# usb.net
KiCad netlist of a schematic drawn in Altium Designer
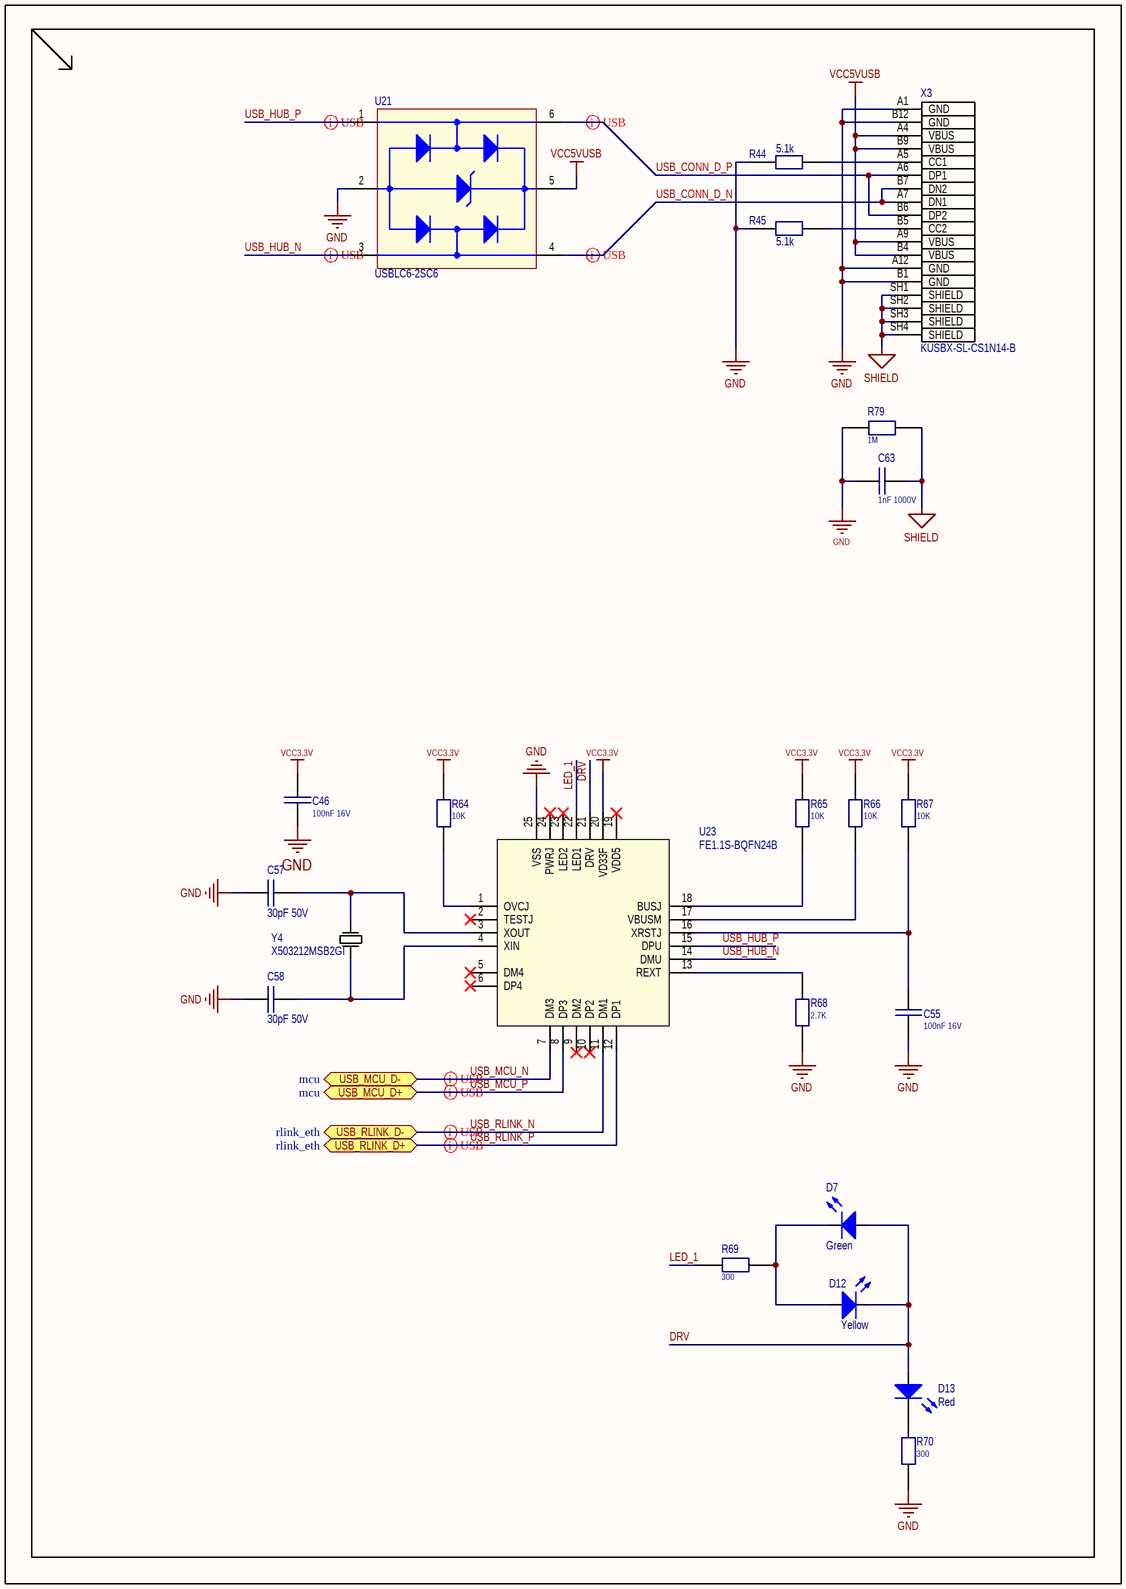
[diagram p0: usb.SchDoc]

(export (version "E")
  (design (tool "Eeschema 10.0.6"))
  (components
    (comp (ref "C46")
      (value "100nF 16V")
      (footprint "C_0402")
      (description "Capacitor")
      (fields (field (name "PART") "CC0402KRX7R7BB104") (field (name "ALTERNATIVE PART") "CC0402KRX5R7BB104"))
      (libsource (lib "capacitors") (part "C0402"))
    )
    (comp (ref "C55")
      (value "100nF 16V")
      (footprint "C_0402")
      (description "Capacitor")
      (fields (field (name "PART") "CC0402KRX7R7BB104") (field (name "ALTERNATIVE PART") "CC0402KRX5R7BB104"))
      (libsource (lib "capacitors") (part "C0402"))
    )
    (comp (ref "C57")
      (value "30pF 50V")
      (footprint "C_0603")
      (description "Capacitor")
      (fields (field (name "PART") "CC0603JRNPO9BN300") (field (name "JLCPCB PART") "C113797"))
      (libsource (lib "capacitors") (part "CAP_SMD"))
    )
    (comp (ref "C58")
      (value "30pF 50V")
      (footprint "C_0603")
      (description "Capacitor")
      (fields (field (name "PART") "CC0603JRNPO9BN300") (field (name "JLCPCB PART") "C113797"))
      (libsource (lib "capacitors") (part "CAP_SMD"))
    )
    (comp (ref "C63")
      (value "1nF 1000V")
      (footprint "C_1206")
      (description "Capacitor")
      (fields (field (name "PART") "CC1206KKX7RCBB102") (field (name "ALTERNATIVE PART") "CL31B102KIFNNNE"))
      (libsource (lib "capacitors") (part "C1206"))
    )
    (comp (ref "D7")
      (value "Green")
      (footprint "LED_0603")
      (description "LED")
      (fields (field (name "PART") "FYLS-0603PGC") (field (name "ALTERNATIVE PART") "KP-1608CGCK"))
      (libsource (lib "led_lcd") (part "LED_SMT_0603"))
    )
    (comp (ref "D12")
      (value "Yellow")
      (footprint "LED_0603")
      (description "LED")
      (fields (field (name "PART") "FYLS-0603PGC") (field (name "ALTERNATIVE PART") "KP-1608CGCK"))
      (libsource (lib "led_lcd") (part "LED_SMT_0603"))
    )
    (comp (ref "D13")
      (value "Red")
      (footprint "LED_0603")
      (description "LED")
      (fields (field (name "PART") "FYLS-0603PGC") (field (name "ALTERNATIVE PART") "KP-1608CGCK"))
      (libsource (lib "led_lcd") (part "LED_SMT_0603"))
    )
    (comp (ref "R44")
      (value "5.1k")
      (footprint "R_0603")
      (description "Resistor")
      (fields (field (name "PART") "RC0603JR-075K1L") (field (name "JLCPCB PART") "C14677"))
      (libsource (lib "resistors") (part "RES_SMD"))
    )
    (comp (ref "R45")
      (value "5.1k")
      (footprint "R_0603")
      (description "Resistor")
      (fields (field (name "PART") "RC0603JR-075K1L") (field (name "JLCPCB PART") "C14677"))
      (libsource (lib "resistors") (part "RES_SMD"))
    )
    (comp (ref "R64")
      (value "10K")
      (footprint "R_0402")
      (description "Resistor")
      (fields (field (name "PART") "RC0402JR-0710KL") (field (name "JLCPCB PART") "C60489"))
      (libsource (lib "resistors") (part "R0402"))
    )
    (comp (ref "R65")
      (value "10K")
      (footprint "R_0402")
      (description "Resistor")
      (fields (field (name "PART") "RC0402JR-0710KL") (field (name "JLCPCB PART") "C60489"))
      (libsource (lib "resistors") (part "R0402"))
    )
    (comp (ref "R66")
      (value "10K")
      (footprint "R_0402")
      (description "Resistor")
      (fields (field (name "PART") "RC0402JR-0710KL") (field (name "JLCPCB PART") "C60489"))
      (libsource (lib "resistors") (part "R0402"))
    )
    (comp (ref "R67")
      (value "10K")
      (footprint "R_0402")
      (description "Resistor")
      (fields (field (name "PART") "RC0402JR-0710KL") (field (name "JLCPCB PART") "C60489"))
      (libsource (lib "resistors") (part "R0402"))
    )
    (comp (ref "R68")
      (value "2.7K")
      (footprint "R_0402")
      (description "Resistor")
      (fields (field (name "PART") "RC0402FR-072K7L") (field (name "JLCPCB PART") "C138017"))
      (libsource (lib "resistors") (part "R0402"))
    )
    (comp (ref "R69")
      (value "300")
      (footprint "R_0603")
      (description "Resistor")
      (fields (field (name "PART") "RC0603FR-07300RL") (field (name "JLCPCB PART") "C114617"))
      (libsource (lib "resistors") (part "R0603"))
    )
    (comp (ref "R70")
      (value "300")
      (footprint "R_0603")
      (description "Resistor")
      (fields (field (name "PART") "RC0603FR-07300RL") (field (name "JLCPCB PART") "C114617"))
      (libsource (lib "resistors") (part "R0603"))
    )
    (comp (ref "R79")
      (value "1M")
      (footprint "R_1206")
      (description "Resistor")
      (fields (field (name "PART") "RC1206FR-071ML") (field (name "JLCPCB PART") "C108083"))
      (libsource (lib "resistors") (part "R1206"))
    )
    (comp (ref "U21")
      (value "USBLC6-2SC6")
      (footprint "diode:SOT95P280X145-6N")
      (description "17V Clamp 5A (8/20Âµs) Ipp Tvs Diode Surface Mount SOT-23-6")
      (fields (field (name "MF") "STMicroelectronics") (field (name "JLCPCB PART") "C2827654"))
      (libsource (lib "diode") (part "USBLC6-2SC6"))
    )
    (comp (ref "U23")
      (value "FE1.1S-BQFN24B")
      (footprint "QFN50P400X400X80-25N-D")
      (description "USB 2.0 HIGH SPEED 4-PORT HUB CONTROLLER")
      (fields (field (name "JLCPCB PART") "C6776948"))
      (libsource (lib "discret_ic") (part "FE1.1S-BQFN24B"))
    )
    (comp (ref "X3")
      (value "KUSBX-SL-CS1N14-B")
      (footprint "MOLEX_2169890001")
      (description "USB Connector USB TYPE C UPRIGHT STRAIGHT TAB 14 PIN")
      (fields (field (name "JLCPCB PART") "C2894906"))
      (libsource (lib "connectors_socets") (part "MOLEX_216989-0001"))
    )
    (comp (ref "Y4")
      (value "X503212MSB2GI")
      (footprint "X5032")
      (description "Crystal Oscillator")
      (fields (field (name "JLCPCB PART") "C112573"))
      (libsource (lib "crystals_oscillators") (part "X503212MSB2GI"))
    )
  )
  (nets
    (net (code "1") (name "/DRV") (class "Default")
      (node (ref "D12") (pin "2") (pinfunction "K_2") (pintype "passive"))
      (node (ref "D13") (pin "1") (pinfunction "A_1") (pintype "passive"))
      (node (ref "D7") (pin "1") (pinfunction "A_1") (pintype "passive"))
      (node (ref "U23") (pin "21") (pinfunction "DRV_21") (pintype "passive"))
    )
    (net (code "2") (name "/LED_1") (class "Default")
      (node (ref "R69") (pin "2") (pinfunction "2_2") (pintype "passive"))
      (node (ref "U23") (pin "22") (pinfunction "LED1_22") (pintype "passive"))
    )
    (net (code "3") (name "/USB_CONN_D_N") (class "Default")
      (node (ref "U21") (pin "4") (pinfunction "I/O2_OUT_4") (pintype "passive"))
      (node (ref "X3") (pin "A7") (pinfunction "DN1_A7") (pintype "passive"))
      (node (ref "X3") (pin "B7") (pinfunction "DN2_B7") (pintype "passive"))
    )
    (net (code "4") (name "/USB_CONN_D_P") (class "Default")
      (node (ref "U21") (pin "6") (pinfunction "I/O1_OUT_6") (pintype "passive"))
      (node (ref "X3") (pin "A6") (pinfunction "DP1_A6") (pintype "passive"))
      (node (ref "X3") (pin "B6") (pinfunction "DP2_B6") (pintype "passive"))
    )
    (net (code "5") (name "/USB_HUB_N") (class "Default")
      (node (ref "U21") (pin "3") (pinfunction "I/O2_IN_3") (pintype "passive"))
      (node (ref "U23") (pin "14") (pinfunction "DMU_14") (pintype "passive"))
    )
    (net (code "6") (name "/USB_HUB_P") (class "Default")
      (node (ref "U21") (pin "1") (pinfunction "I/O1_IN_1") (pintype "passive"))
      (node (ref "U23") (pin "15") (pinfunction "DPU_15") (pintype "passive"))
    )
    (net (code "7") (name "/USB_MCU_N") (class "Default")
      (node (ref "U23") (pin "7") (pinfunction "DM3_7") (pintype "passive"))
    )
    (net (code "8") (name "/USB_MCU_P") (class "Default")
      (node (ref "U23") (pin "8") (pinfunction "DP3_8") (pintype "passive"))
    )
    (net (code "9") (name "/USB_RLINK_N") (class "Default")
      (node (ref "U23") (pin "11") (pinfunction "DM1_11") (pintype "passive"))
    )
    (net (code "10") (name "/USB_RLINK_P") (class "Default")
      (node (ref "U23") (pin "12") (pinfunction "DP1_12") (pintype "passive"))
    )
    (net (code "11") (name "GND") (class "Default")
      (node (ref "C46") (pin "1") (pinfunction "1_1") (pintype "passive"))
      (node (ref "C55") (pin "2") (pinfunction "2_2") (pintype "passive"))
      (node (ref "C57") (pin "2") (pinfunction "2_2") (pintype "passive"))
      (node (ref "C58") (pin "2") (pinfunction "2_2") (pintype "passive"))
      (node (ref "C63") (pin "1") (pinfunction "1_1") (pintype "passive"))
      (node (ref "R44") (pin "1") (pinfunction "1_1") (pintype "passive"))
      (node (ref "R45") (pin "1") (pinfunction "1_1") (pintype "passive"))
      (node (ref "R68") (pin "2") (pinfunction "2_2") (pintype "passive"))
      (node (ref "R70") (pin "1") (pinfunction "1_1") (pintype "passive"))
      (node (ref "R79") (pin "1") (pinfunction "1_1") (pintype "passive"))
      (node (ref "U21") (pin "2") (pinfunction "GND_2") (pintype "passive"))
      (node (ref "U23") (pin "25") (pinfunction "VSS_25") (pintype "power_in"))
      (node (ref "X3") (pin "A1") (pinfunction "GND_A1") (pintype "passive"))
      (node (ref "X3") (pin "A12") (pinfunction "GND_A12") (pintype "passive"))
      (node (ref "X3") (pin "B1") (pinfunction "GND_B1") (pintype "passive"))
      (node (ref "X3") (pin "B12") (pinfunction "GND_B12") (pintype "passive"))
    )
    (net (code "12") (name "Net-(D12-A)") (class "Default")
      (node (ref "D12") (pin "1") (pinfunction "A_1") (pintype "passive"))
      (node (ref "D7") (pin "2") (pinfunction "K_2") (pintype "passive"))
      (node (ref "R69") (pin "1") (pinfunction "1_1") (pintype "passive"))
    )
    (net (code "13") (name "Net-(D13-K)") (class "Default")
      (node (ref "D13") (pin "2") (pinfunction "K_2") (pintype "passive"))
      (node (ref "R70") (pin "2") (pinfunction "2_2") (pintype "passive"))
    )
    (net (code "14") (name "Net-(U23-BUSJ)") (class "Default")
      (node (ref "R65") (pin "1") (pinfunction "1_1") (pintype "passive"))
      (node (ref "U23") (pin "18") (pinfunction "BUSJ_18") (pintype "passive"))
    )
    (net (code "15") (name "Net-(U23-OVCJ)") (class "Default")
      (node (ref "R64") (pin "1") (pinfunction "1_1") (pintype "passive"))
      (node (ref "U23") (pin "1") (pinfunction "OVCJ_1") (pintype "passive"))
    )
    (net (code "16") (name "Net-(U23-REXT)") (class "Default")
      (node (ref "R68") (pin "1") (pinfunction "1_1") (pintype "passive"))
      (node (ref "U23") (pin "13") (pinfunction "REXT_13") (pintype "passive"))
    )
    (net (code "17") (name "Net-(U23-VBUSM)") (class "Default")
      (node (ref "R66") (pin "1") (pinfunction "1_1") (pintype "passive"))
      (node (ref "U23") (pin "17") (pinfunction "VBUSM_17") (pintype "passive"))
    )
    (net (code "18") (name "Net-(U23-XIN)") (class "Default")
      (node (ref "C58") (pin "1") (pinfunction "1_1") (pintype "passive"))
      (node (ref "U23") (pin "4") (pinfunction "XIN_4") (pintype "passive"))
      (node (ref "Y4") (pin "2") (pinfunction "2_2") (pintype "passive"))
    )
    (net (code "19") (name "Net-(U23-XOUT)") (class "Default")
      (node (ref "C57") (pin "1") (pinfunction "1_1") (pintype "passive"))
      (node (ref "U23") (pin "3") (pinfunction "XOUT_3") (pintype "passive"))
      (node (ref "Y4") (pin "1") (pinfunction "1_1") (pintype "passive"))
    )
    (net (code "20") (name "Net-(U23-XRSTJ)") (class "Default")
      (node (ref "C55") (pin "1") (pinfunction "1_1") (pintype "passive"))
      (node (ref "R67") (pin "1") (pinfunction "1_1") (pintype "passive"))
      (node (ref "U23") (pin "16") (pinfunction "XRSTJ_16") (pintype "passive"))
    )
    (net (code "21") (name "Net-(X3-CC1)") (class "Default")
      (node (ref "R44") (pin "2") (pinfunction "2_2") (pintype "passive"))
      (node (ref "X3") (pin "A5") (pinfunction "CC1_A5") (pintype "passive"))
    )
    (net (code "22") (name "Net-(X3-CC2)") (class "Default")
      (node (ref "R45") (pin "2") (pinfunction "2_2") (pintype "passive"))
      (node (ref "X3") (pin "B5") (pinfunction "CC2_B5") (pintype "passive"))
    )
    (net (code "23") (name "SHIELD") (class "Default")
      (node (ref "C63") (pin "2") (pinfunction "2_2") (pintype "passive"))
      (node (ref "R79") (pin "2") (pinfunction "2_2") (pintype "passive"))
      (node (ref "X3") (pin "SH1") (pinfunction "SHIELD_SH1") (pintype "passive"))
      (node (ref "X3") (pin "SH2") (pinfunction "SHIELD_SH2") (pintype "passive"))
      (node (ref "X3") (pin "SH3") (pinfunction "SHIELD_SH3") (pintype "passive"))
      (node (ref "X3") (pin "SH4") (pinfunction "SHIELD_SH4") (pintype "passive"))
    )
    (net (code "24") (name "VCC3.3V") (class "Default")
      (node (ref "C46") (pin "2") (pinfunction "2_2") (pintype "passive"))
      (node (ref "R64") (pin "2") (pinfunction "2_2") (pintype "passive"))
      (node (ref "R65") (pin "2") (pinfunction "2_2") (pintype "passive"))
      (node (ref "R66") (pin "2") (pinfunction "2_2") (pintype "passive"))
      (node (ref "R67") (pin "2") (pinfunction "2_2") (pintype "passive"))
      (node (ref "U23") (pin "20") (pinfunction "VD33F_20") (pintype "power_in"))
    )
    (net (code "25") (name "VCC5VUSB") (class "Default")
      (node (ref "U21") (pin "5") (pinfunction "VBUS_5") (pintype "passive"))
      (node (ref "X3") (pin "A4") (pinfunction "VBUS_A4") (pintype "passive"))
      (node (ref "X3") (pin "A9") (pinfunction "VBUS_A9") (pintype "passive"))
      (node (ref "X3") (pin "B4") (pinfunction "VBUS_B4") (pintype "passive"))
      (node (ref "X3") (pin "B9") (pinfunction "VBUS_B9") (pintype "passive"))
    )
    (net (code "26") (name "unconnected-(U23-DM2-Pad9)") (class "Default")
      (node (ref "U23") (pin "9") (pinfunction "DM2_9") (pintype "passive+no_connect"))
    )
    (net (code "27") (name "unconnected-(U23-DM4-Pad5)") (class "Default")
      (node (ref "U23") (pin "5") (pinfunction "DM4_5") (pintype "passive+no_connect"))
    )
    (net (code "28") (name "unconnected-(U23-DP2-Pad10)") (class "Default")
      (node (ref "U23") (pin "10") (pinfunction "DP2_10") (pintype "passive+no_connect"))
    )
    (net (code "29") (name "unconnected-(U23-DP4-Pad6)") (class "Default")
      (node (ref "U23") (pin "6") (pinfunction "DP4_6") (pintype "passive+no_connect"))
    )
    (net (code "30") (name "unconnected-(U23-LED2-Pad23)") (class "Default")
      (node (ref "U23") (pin "23") (pinfunction "LED2_23") (pintype "passive+no_connect"))
    )
    (net (code "31") (name "unconnected-(U23-PWRJ-Pad24)") (class "Default")
      (node (ref "U23") (pin "24") (pinfunction "PWRJ_24") (pintype "passive+no_connect"))
    )
    (net (code "32") (name "unconnected-(U23-TESTJ-Pad2)") (class "Default")
      (node (ref "U23") (pin "2") (pinfunction "TESTJ_2") (pintype "passive+no_connect"))
    )
    (net (code "33") (name "unconnected-(U23-VDD5-Pad19)") (class "Default")
      (node (ref "U23") (pin "19") (pinfunction "VDD5_19") (pintype "power_in+no_connect"))
    )
  )
)
